# LMV324__20260912.net
KiCad netlist of a schematic drawn in Altium Designer
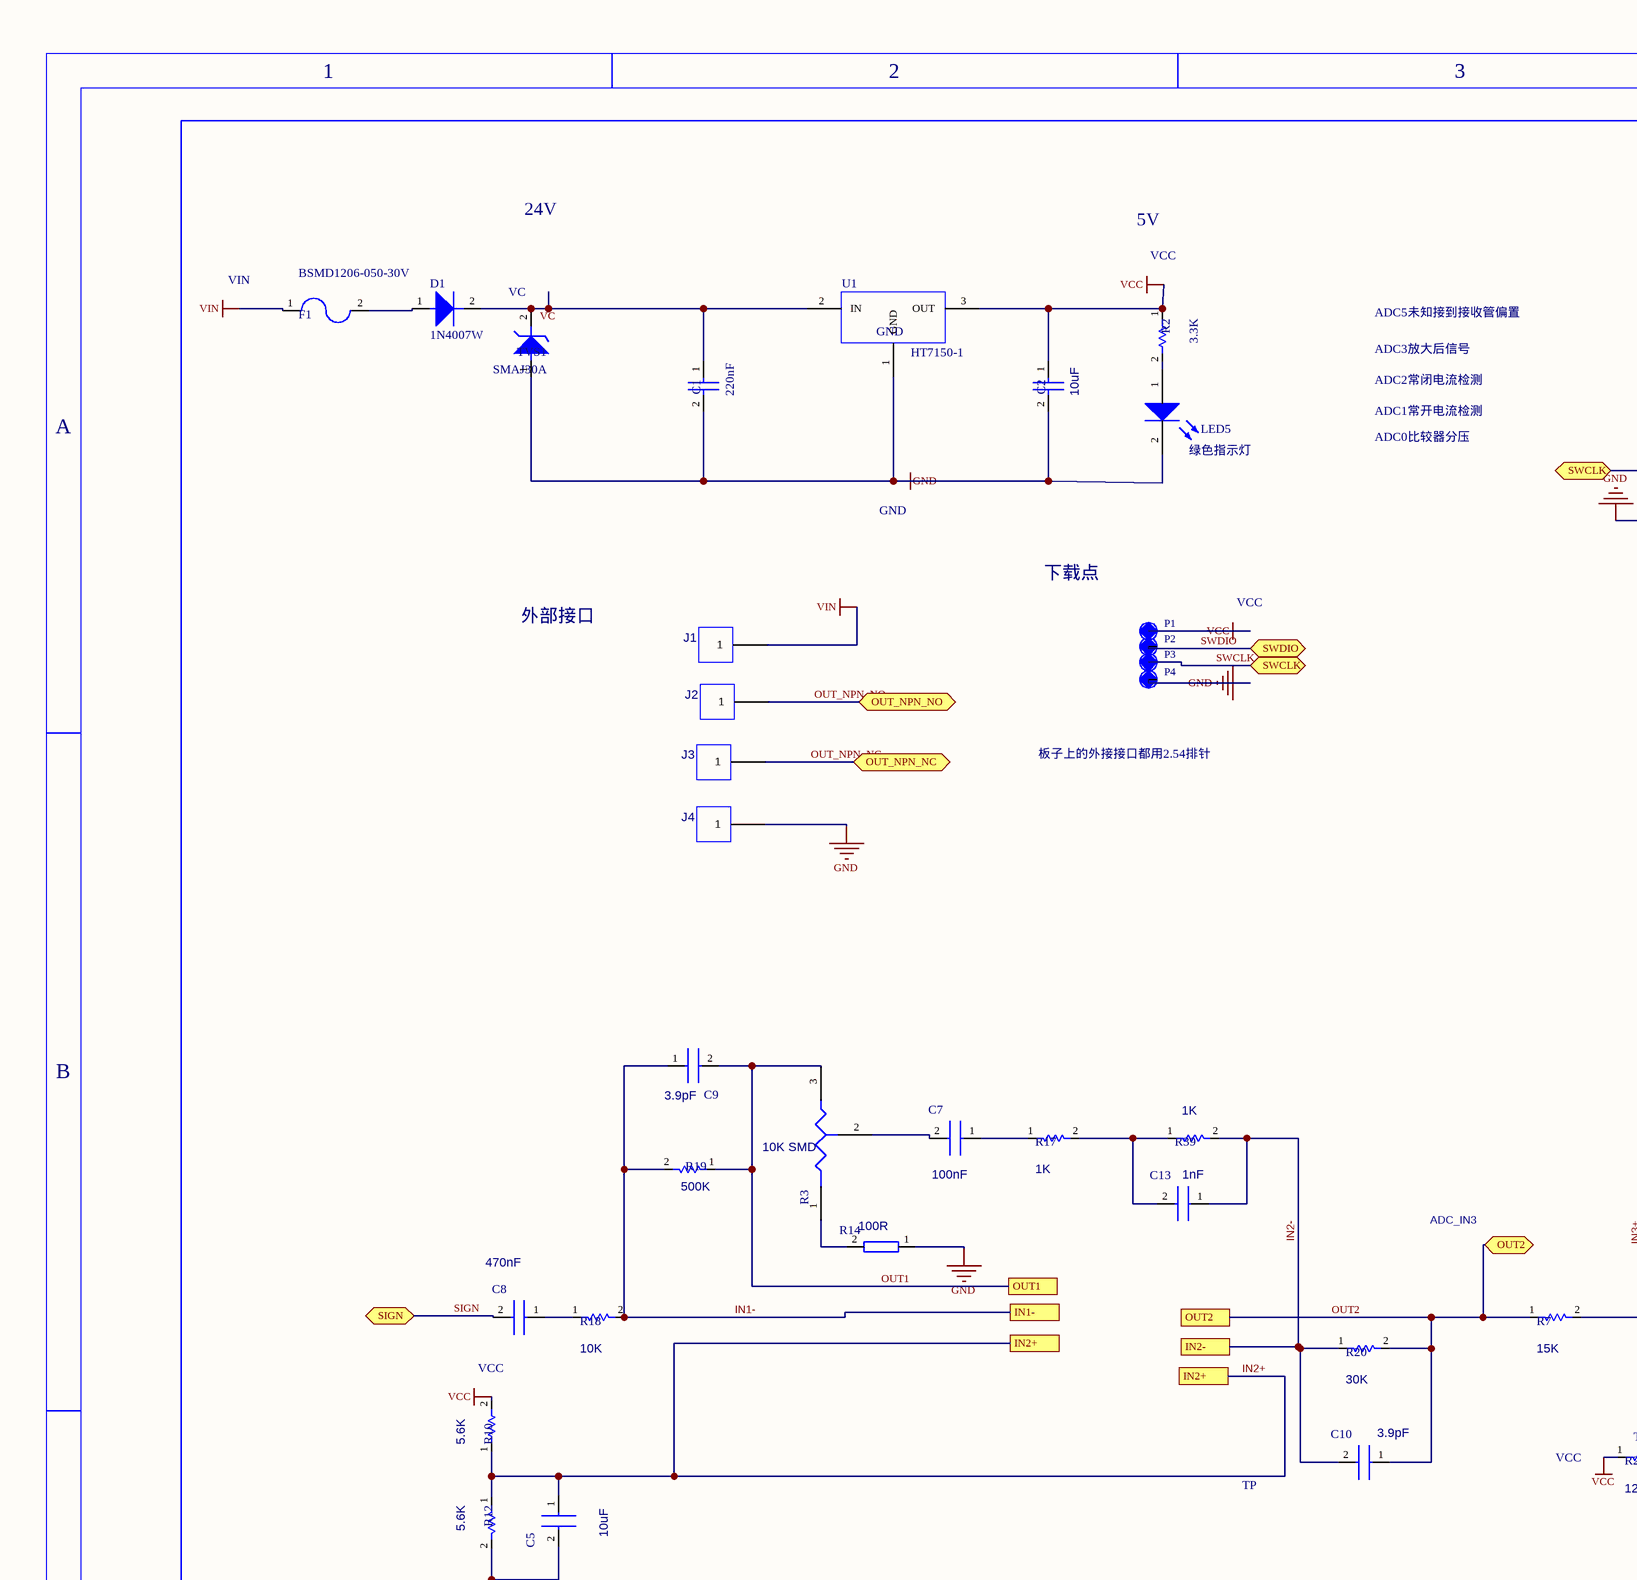
[diagram p0: LMV324对射发射板_20260912.SchDoc, top left]
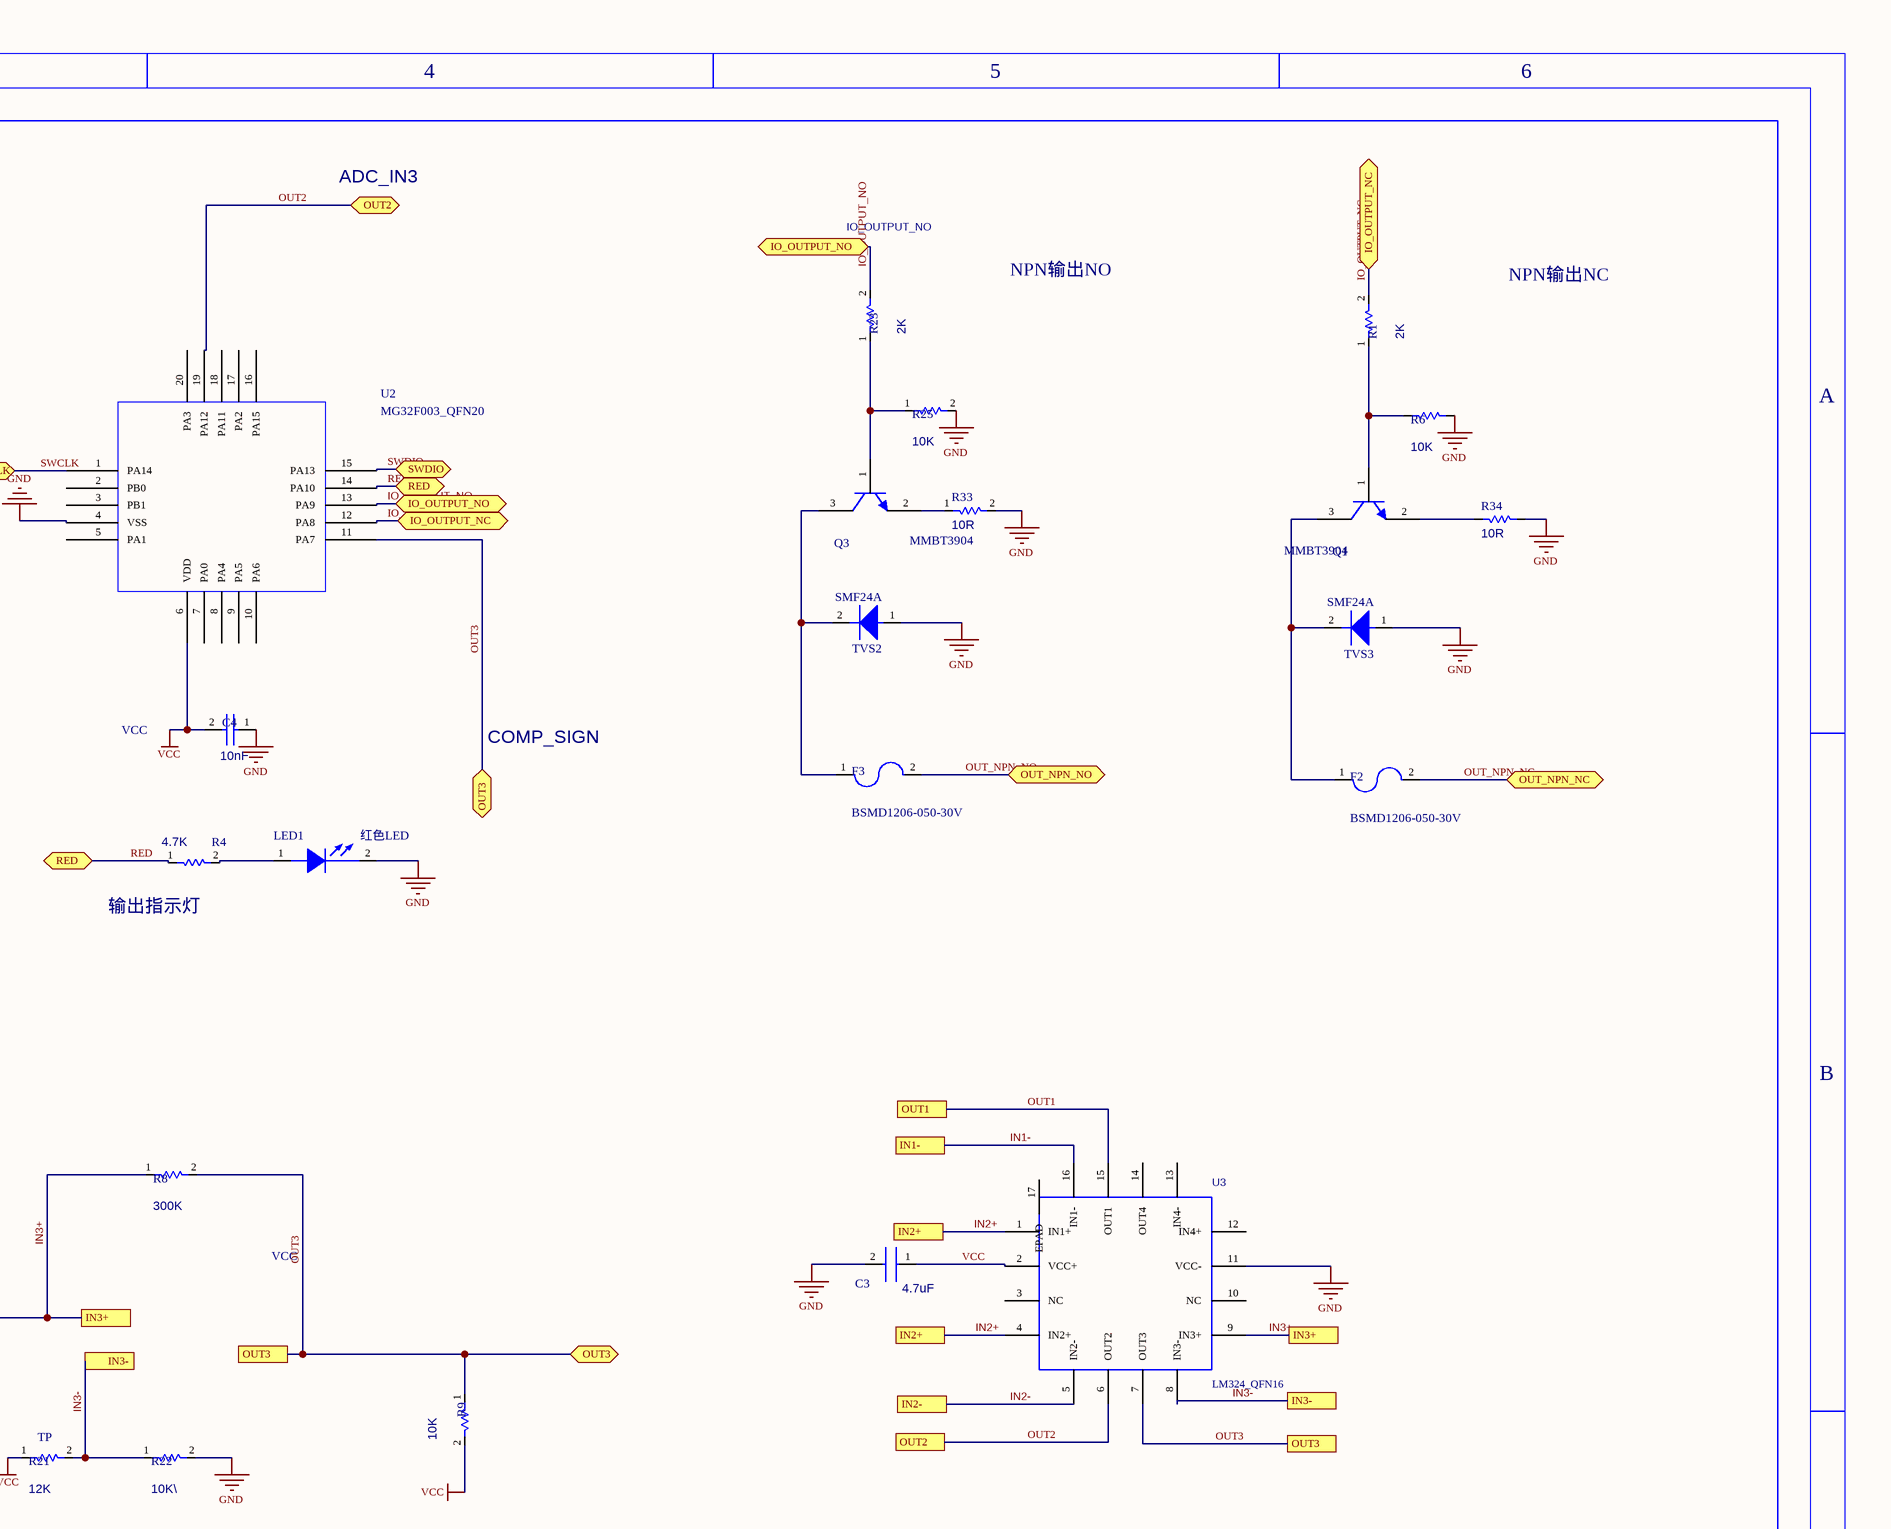
[diagram p1: LMV324对射发射板_20260912.SchDoc, top right]
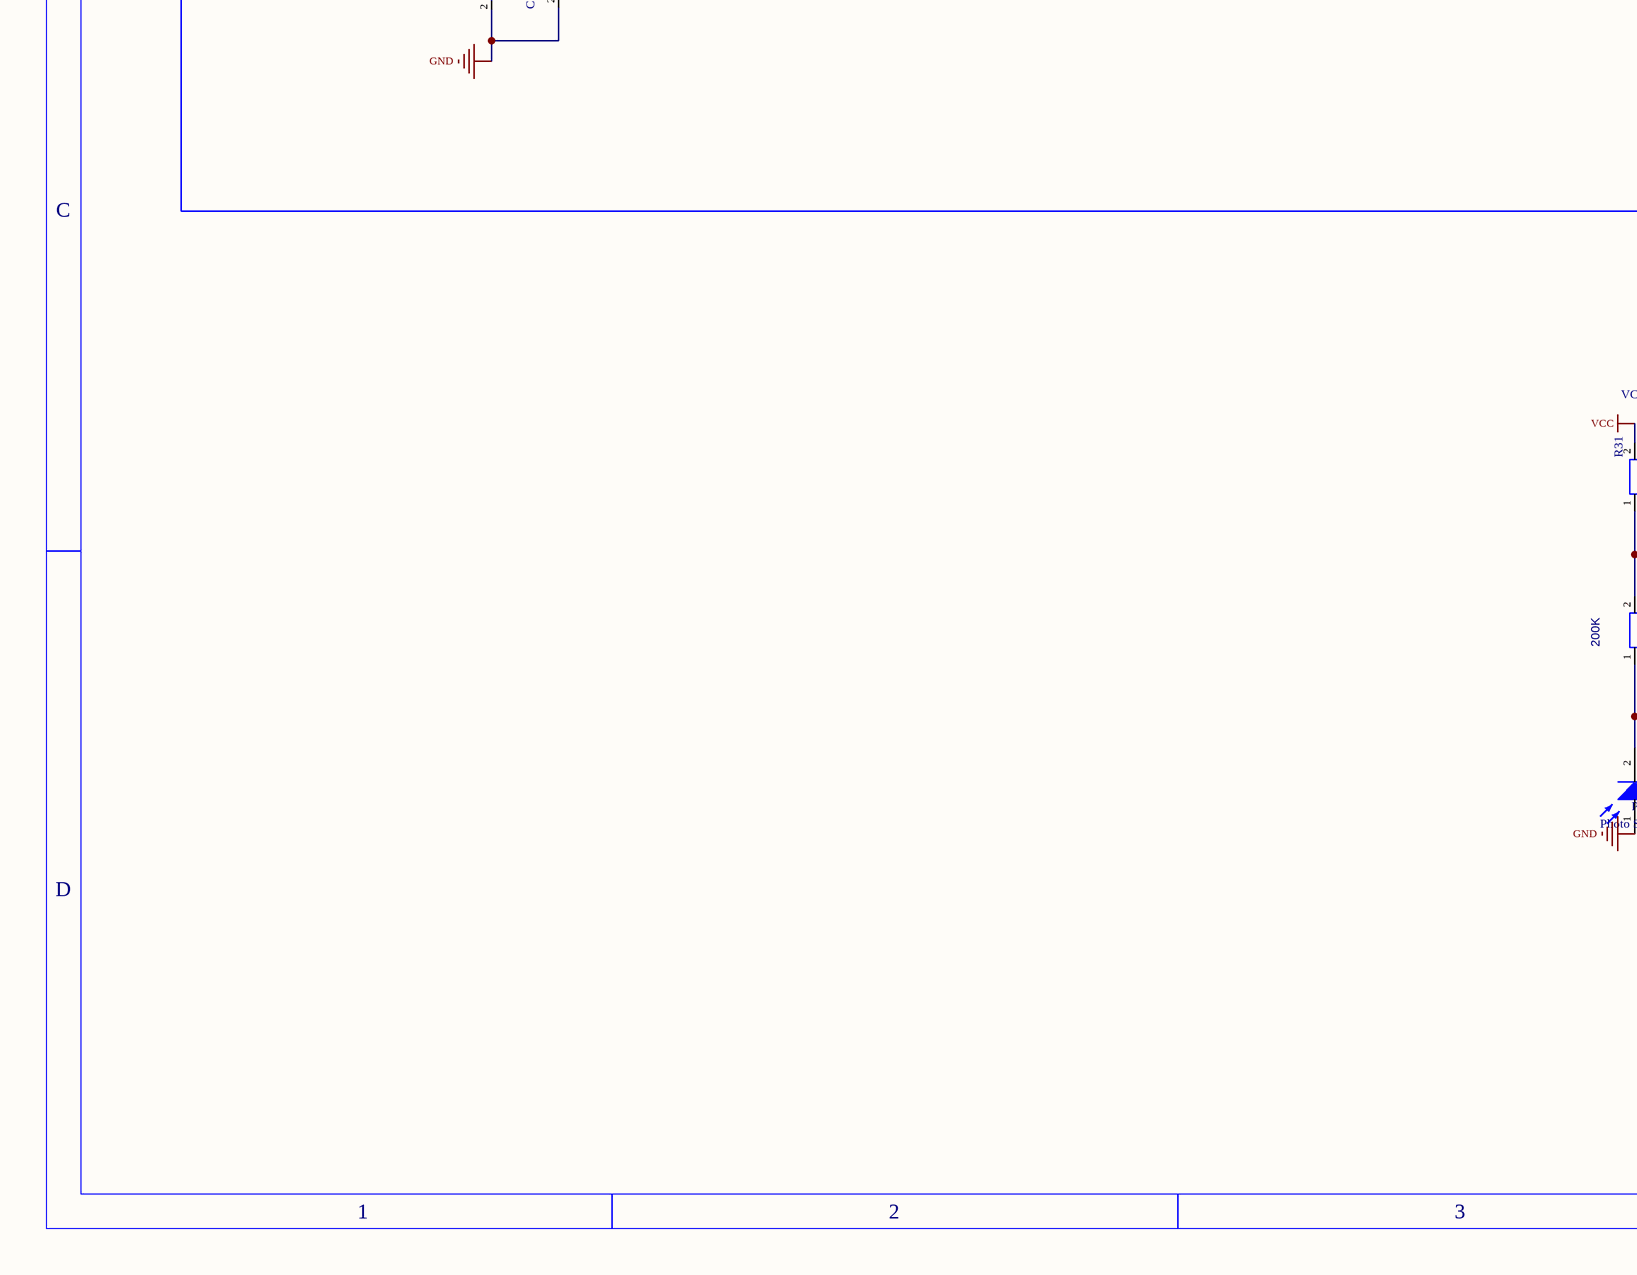
[diagram p2: LMV324对射发射板_20260912.SchDoc, bottom left]
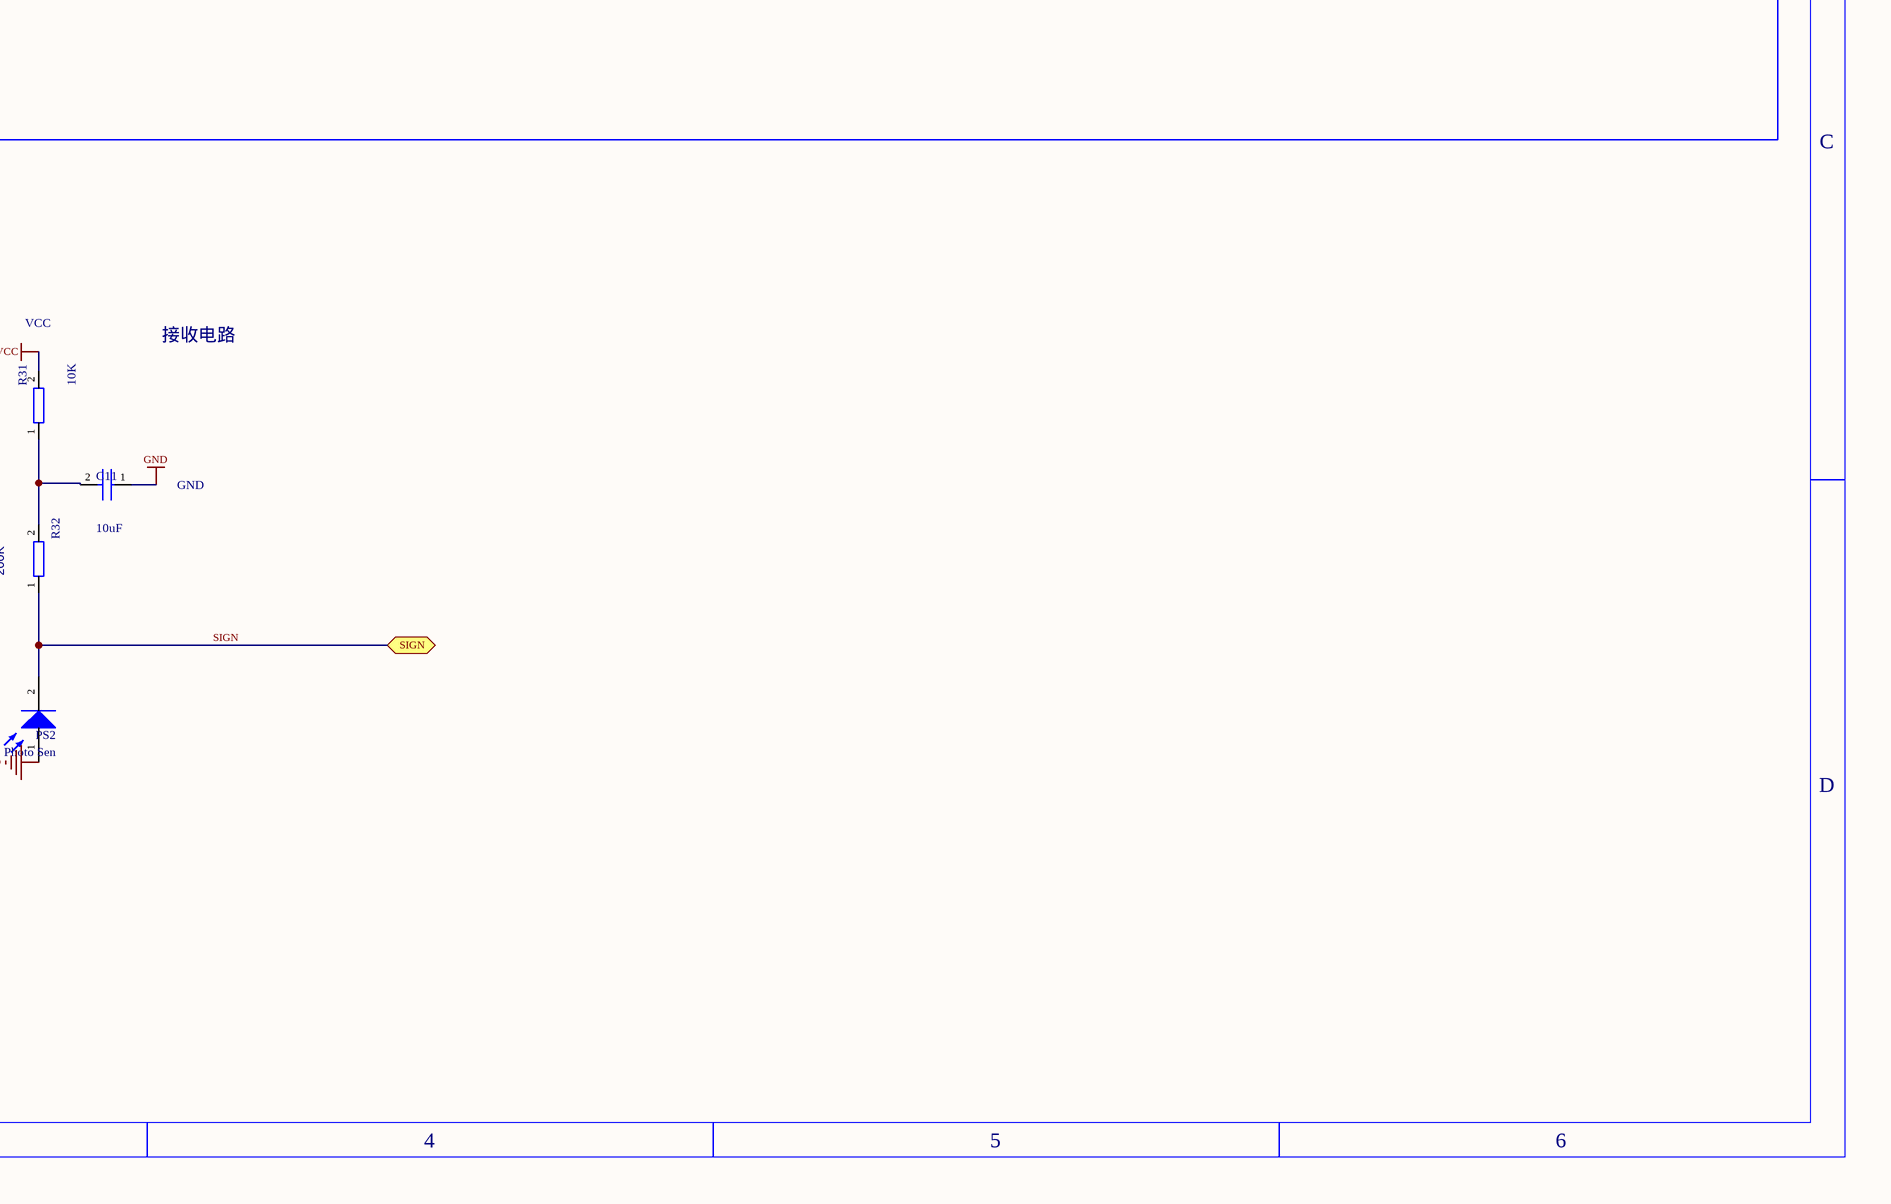
[diagram p3: LMV324对射发射板_20260912.SchDoc, bottom right]

(export (version "E")
  (design (tool "Eeschema 10.0.6"))
  (components
    (comp (ref "C1")
      (value "CAP")
      (footprint "C0603")
      (description "陶瓷电容")
      (libsource (lib "*") (part "CAP"))
    )
    (comp (ref "C2")
      (value "CAP")
      (footprint "C0603")
      (description "陶瓷电容")
      (libsource (lib "*") (part "CAP"))
    )
    (comp (ref "C3") (value "CAP_2") (footprint "C0603") (libsource (lib "*") (part "CAP_2")))
    (comp (ref "C4")
      (value "CAP")
      (footprint "C0603")
      (description "陶瓷电容")
      (libsource (lib "*") (part "CAP"))
    )
    (comp (ref "C5") (value "CAP_2") (footprint "C0603") (libsource (lib "*") (part "CAP_2")))
    (comp (ref "C7")
      (value "CAP0402")
      (footprint "0402C")
      (description "Capacitor")
      (libsource (lib "*") (part "CAP0402"))
    )
    (comp (ref "C8")
      (value "CAP0402")
      (footprint "0402C")
      (description "Capacitor")
      (libsource (lib "*") (part "CAP0402"))
    )
    (comp (ref "C9")
      (value "CAP0402")
      (footprint "0402C")
      (description "Capacitor")
      (libsource (lib "*") (part "CAP0402"))
    )
    (comp (ref "C10")
      (value "CAP0402")
      (footprint "0402C")
      (description "Capacitor")
      (libsource (lib "*") (part "CAP0402"))
    )
    (comp (ref "C11") (value "CAP_NP") (footprint "0603") (libsource (lib "*") (part "CAP_NP")))
    (comp (ref "C13")
      (value "CAP0402")
      (footprint "0402C")
      (description "Capacitor")
      (libsource (lib "*") (part "CAP0402"))
    )
    (comp (ref "D1")
      (value "DIODE")
      (footprint "WSOD-323")
      (description "Diode")
      (libsource (lib "*") (part "DIODE"))
    )
    (comp (ref "F1")
      (value "FUSE")
      (footprint "0603")
      (description "Fuse")
      (libsource (lib "") (part "FUSE_1"))
    )
    (comp (ref "F2")
      (value "FUSE")
      (footprint "0603")
      (description "Fuse")
      (libsource (lib "*") (part "FUSE"))
    )
    (comp (ref "F3")
      (value "FUSE")
      (footprint "0603")
      (description "Fuse")
      (libsource (lib "*") (part "FUSE"))
    )
    (comp (ref "J1")
      (value "FPAD_3C")
      (footprint "FPAD_3C")
      (description "Connector")
      (libsource (lib "*") (part "FPAD_3C"))
    )
    (comp (ref "J2")
      (value "FPAD_3C")
      (footprint "FPAD_3C")
      (description "Connector")
      (libsource (lib "*") (part "FPAD_3C"))
    )
    (comp (ref "J3")
      (value "FPAD_3C")
      (footprint "FPAD_3C")
      (description "Connector")
      (libsource (lib "*") (part "FPAD_3C"))
    )
    (comp (ref "J4")
      (value "FPAD_3C")
      (footprint "FPAD_3C")
      (description "Connector")
      (libsource (lib "*") (part "FPAD_3C"))
    )
    (comp (ref "LED1") (value "LED") (footprint "LED0603") (libsource (lib "*") (part "LED")))
    (comp (ref "LED5")
      (value "LED2")
      (footprint "LED0603")
      (description "Typical RED, GREEN, YELLOW, AMBER GaAs LED")
      (fields (field (name "PUBLISHER") "Altium Limited"))
      (libsource (lib "*") (part "LED2"))
    )
    (comp (ref "P1")
      (value "TEST_POINTB+")
      (footprint "TEST-POINT_D1.0")
      (libsource (lib "*") (part "TEST_POINTB+"))
    )
    (comp (ref "P2")
      (value "TEST_POINTB+")
      (footprint "TEST-POINT_D1.0")
      (libsource (lib "*") (part "TEST_POINTB+"))
    )
    (comp (ref "P3")
      (value "TEST_POINTB+")
      (footprint "TEST-POINT_D1.0")
      (libsource (lib "*") (part "TEST_POINTB+"))
    )
    (comp (ref "P4")
      (value "TEST_POINTB+")
      (footprint "TEST-POINT_D1.0")
      (libsource (lib "*") (part "TEST_POINTB+"))
    )
    (comp (ref "PS2")
      (value "PHOTO_SEN")
      (footprint "RXLED_SMD")
      (description "Photosensitive Diode")
      (fields (field (name "PUBLISHER") "Altium Limited"))
      (libsource (lib "*") (part "PHOTO_SEN"))
    )
    (comp (ref "Q1")
      (value "NPN")
      (footprint "SOT23/2")
      (description "NPN Bipolar Transistor")
      (fields (field (name "PUBLISHER") "Altium Limited"))
      (libsource (lib "*") (part "NPN"))
    )
    (comp (ref "Q3")
      (value "NPNSOT23")
      (footprint "SOT23/2")
      (description "NPN Bipolar Transistor")
      (fields (field (name "PUBLISHER") "Altium Limited"))
      (libsource (lib "*") (part "NPNSOT23"))
    )
    (comp (ref "R1") (value "RAS0402") (footprint "R0402") (libsource (lib "*") (part "RAS0402")))
    (comp (ref "R2") (value "RAS0402") (footprint "R0402") (libsource (lib "*") (part "RAS0402")))
    (comp (ref "R3")
      (value "10K SMD")
      (footprint "SMD")
      (description "Tapped Resistor")
      (fields (field (name "Comment") "ADJ_SMD") (field (name "PUBLISHER") "Altium Limited"))
      (libsource (lib "*") (part "ADJ_SMD"))
    )
    (comp (ref "R4") (value "RAS") (footprint "0603") (libsource (lib "*") (part "RAS")))
    (comp (ref "R6") (value "RAS0402") (footprint "R0402") (libsource (lib "") (part "RAS0402_1")))
    (comp (ref "R7") (value "RAS0402") (footprint "R0402") (libsource (lib "*") (part "RAS0402")))
    (comp (ref "R8") (value "RAS0402") (footprint "R0402") (libsource (lib "*") (part "RAS0402")))
    (comp (ref "R9") (value "RAS0402") (footprint "R0402") (libsource (lib "*") (part "RAS0402")))
    (comp (ref "R10") (value "RAS0402") (footprint "R0402") (libsource (lib "*") (part "RAS0402")))
    (comp (ref "R12") (value "RAS0402") (footprint "R0402") (libsource (lib "*") (part "RAS0402")))
    (comp (ref "R14") (value "RES") (footprint "R0603") (libsource (lib "*") (part "RES")))
    (comp (ref "R17") (value "RAS0402") (footprint "R0402") (libsource (lib "*") (part "RAS0402")))
    (comp (ref "R18") (value "RAS0402") (footprint "R0402") (libsource (lib "*") (part "RAS0402")))
    (comp (ref "R19") (value "RAS0402") (footprint "R0402") (libsource (lib "*") (part "RAS0402")))
    (comp (ref "R20") (value "RAS0402") (footprint "R0402") (libsource (lib "*") (part "RAS0402")))
    (comp (ref "R21") (value "RAS0402") (footprint "R0402") (libsource (lib "*") (part "RAS0402")))
    (comp (ref "R22") (value "RAS0402") (footprint "R0402") (libsource (lib "*") (part "RAS0402")))
    (comp (ref "R23") (value "RAS0402") (footprint "R0402") (libsource (lib "*") (part "RAS0402")))
    (comp (ref "R25") (value "RAS0402") (footprint "R0402") (libsource (lib "*") (part "RAS0402")))
    (comp (ref "R31") (value "R0402") (footprint "RES0402") (libsource (lib "*") (part "R0402")))
    (comp (ref "R32") (value "R0402") (footprint "RES0402") (libsource (lib "*") (part "R0402")))
    (comp (ref "R33") (value "RAS") (footprint "0603") (libsource (lib "*") (part "RAS")))
    (comp (ref "R34") (value "RAS") (footprint "0603") (libsource (lib "") (part "RAS_1")))
    (comp (ref "R39") (value "RAS0402") (footprint "R0402") (libsource (lib "*") (part "RAS0402")))
    (comp (ref "TVS1")
      (value "DIODE_V")
      (footprint "SOD_523")
      (description "Varactor Diode")
      (libsource (lib "*") (part "DIODE_V"))
    )
    (comp (ref "TVS2")
      (value "SOD523")
      (footprint "SOD_523")
      (description "Diode")
      (fields (field (name "PUBLISHER") "Altium Limited"))
      (libsource (lib "*") (part "SOD523"))
    )
    (comp (ref "TVS3")
      (value "SOD523")
      (footprint "SOD_523")
      (description "Diode")
      (fields (field (name "PUBLISHER") "Altium Limited"))
      (libsource (lib "*") (part "SOD523"))
    )
    (comp (ref "U1")
      (value "HT7530-1")
      (footprint "SOT89")
      (description "3.0V 100mA Low Power,  Low Dropout Voltage (LDO) Regulator")
      (fields (field (name "PUBLISHER") "Altium Limited"))
      (libsource (lib "*") (part "HT7530-1"))
    )
    (comp (ref "U2")
      (value "MG32F003-QFN20")
      (footprint "MG32F003_QFN20")
      (description "QFN20主控芯片")
      (libsource (lib "*") (part "MG32F003-QFN20"))
    )
    (comp (ref "U3")
      (value "LM324_QFN16")
      (footprint "LM324_QFN16")
      (libsource (lib "*") (part "LM324_QFN16"))
    )
  )
  (nets
    (net (code "1") (name "/IN1-") (class "Default")
      (node (ref "C9") (pin "1") (pinfunction "1_1") (pintype "passive"))
      (node (ref "R18") (pin "2") (pinfunction "2_2") (pintype "passive"))
      (node (ref "R19") (pin "2") (pinfunction "2_2") (pintype "passive"))
      (node (ref "U3") (pin "16") (pinfunction "IN1-_16") (pintype "passive"))
    )
    (net (code "2") (name "/IN2+") (class "Default")
      (node (ref "C5") (pin "1") (pinfunction "1_1") (pintype "passive"))
      (node (ref "R10") (pin "1") (pinfunction "1_1") (pintype "passive"))
      (node (ref "R12") (pin "1") (pinfunction "1_1") (pintype "passive"))
      (node (ref "U3") (pin "1") (pinfunction "IN1+_1") (pintype "passive"))
      (node (ref "U3") (pin "4") (pinfunction "IN2+_4") (pintype "passive"))
    )
    (net (code "3") (name "/IN2-") (class "Default")
      (node (ref "C10") (pin "2") (pinfunction "2_2") (pintype "passive"))
      (node (ref "C13") (pin "1") (pinfunction "1_1") (pintype "passive"))
      (node (ref "R20") (pin "1") (pinfunction "1_1") (pintype "passive"))
      (node (ref "R39") (pin "2") (pinfunction "2_2") (pintype "passive"))
      (node (ref "U3") (pin "5") (pinfunction "IN2-_5") (pintype "passive"))
    )
    (net (code "4") (name "/IN3+") (class "Default")
      (node (ref "R7") (pin "2") (pinfunction "2_2") (pintype "passive"))
      (node (ref "R8") (pin "1") (pinfunction "1_1") (pintype "passive"))
      (node (ref "U3") (pin "9") (pinfunction "IN3+_9") (pintype "passive"))
    )
    (net (code "5") (name "/IN3-") (class "Default")
      (node (ref "R21") (pin "2") (pinfunction "2_2") (pintype "passive"))
      (node (ref "R22") (pin "1") (pinfunction "1_1") (pintype "passive"))
      (node (ref "U3") (pin "8") (pinfunction "IN3-_8") (pintype "passive"))
    )
    (net (code "6") (name "/IO_OUTPUT_NC") (class "Default")
      (node (ref "R1") (pin "2") (pinfunction "2_2") (pintype "passive"))
      (node (ref "U2") (pin "12") (pinfunction "PA8_12") (pintype "passive"))
    )
    (net (code "7") (name "/IO_OUTPUT_NO") (class "Default")
      (node (ref "R23") (pin "2") (pinfunction "2_2") (pintype "passive"))
      (node (ref "U2") (pin "13") (pinfunction "PA9_13") (pintype "passive"))
    )
    (net (code "8") (name "/OUT1") (class "Default")
      (node (ref "C9") (pin "2") (pinfunction "2_2") (pintype "passive"))
      (node (ref "R19") (pin "1") (pinfunction "1_1") (pintype "passive"))
      (node (ref "R3") (pin "3") (pinfunction "A_3") (pintype "passive"))
      (node (ref "U3") (pin "15") (pinfunction "OUT1_15") (pintype "passive"))
    )
    (net (code "9") (name "/OUT2") (class "Default")
      (node (ref "C10") (pin "1") (pinfunction "1_1") (pintype "passive"))
      (node (ref "R20") (pin "2") (pinfunction "2_2") (pintype "passive"))
      (node (ref "R7") (pin "1") (pinfunction "1_1") (pintype "passive"))
      (node (ref "U2") (pin "19") (pinfunction "PA12_19") (pintype "passive"))
      (node (ref "U3") (pin "6") (pinfunction "OUT2_6") (pintype "passive"))
    )
    (net (code "10") (name "/OUT3") (class "Default")
      (node (ref "R8") (pin "2") (pinfunction "2_2") (pintype "passive"))
      (node (ref "R9") (pin "1") (pinfunction "1_1") (pintype "passive"))
      (node (ref "U2") (pin "11") (pinfunction "PA7_11") (pintype "passive"))
      (node (ref "U3") (pin "7") (pinfunction "OUT3_7") (pintype "passive"))
    )
    (net (code "11") (name "/OUT_NPN_NC") (class "Default")
      (node (ref "F2") (pin "2") (pinfunction "2_2") (pintype "passive"))
      (node (ref "J3") (pin "1") (pinfunction "1_1") (pintype "passive"))
    )
    (net (code "12") (name "/OUT_NPN_NO") (class "Default")
      (node (ref "F3") (pin "2") (pinfunction "2_2") (pintype "passive"))
      (node (ref "J2") (pin "1") (pinfunction "1_1") (pintype "passive"))
    )
    (net (code "13") (name "/RED") (class "Default")
      (node (ref "R4") (pin "1") (pinfunction "1_1") (pintype "passive"))
      (node (ref "U2") (pin "14") (pinfunction "PA10_14") (pintype "passive"))
    )
    (net (code "14") (name "/SIGN") (class "Default")
      (node (ref "C8") (pin "2") (pinfunction "2_2") (pintype "passive"))
      (node (ref "PS2") (pin "2") (pinfunction "K_2") (pintype "passive"))
      (node (ref "R32") (pin "1") (pinfunction "1_1") (pintype "passive"))
    )
    (net (code "15") (name "/SWCLK") (class "Default")
      (node (ref "P3") (pin "1") (pinfunction "1_1") (pintype "passive"))
      (node (ref "U2") (pin "1") (pinfunction "PA14_1") (pintype "passive"))
    )
    (net (code "16") (name "/SWDIO") (class "Default")
      (node (ref "P2") (pin "1") (pinfunction "1_1") (pintype "passive"))
      (node (ref "U2") (pin "15") (pinfunction "PA13_15") (pintype "passive"))
    )
    (net (code "17") (name "GND") (class "Default")
      (node (ref "C1") (pin "2") (pinfunction "2_2") (pintype "passive"))
      (node (ref "C11") (pin "1") (pinfunction "1_1") (pintype "passive"))
      (node (ref "C2") (pin "2") (pinfunction "2_2") (pintype "passive"))
      (node (ref "C3") (pin "2") (pinfunction "2_2") (pintype "passive"))
      (node (ref "C4") (pin "1") (pinfunction "1_1") (pintype "passive"))
      (node (ref "C5") (pin "2") (pinfunction "2_2") (pintype "passive"))
      (node (ref "J4") (pin "1") (pinfunction "1_1") (pintype "passive"))
      (node (ref "LED1") (pin "2") (pinfunction "CATHODE_2") (pintype "passive"))
      (node (ref "LED5") (pin "2") (pinfunction "K_2") (pintype "passive"))
      (node (ref "P4") (pin "1") (pinfunction "1_1") (pintype "passive"))
      (node (ref "PS2") (pin "1") (pinfunction "A_1") (pintype "passive"))
      (node (ref "R12") (pin "2") (pinfunction "2_2") (pintype "passive"))
      (node (ref "R14") (pin "1") (pinfunction "1_1") (pintype "passive"))
      (node (ref "R22") (pin "2") (pinfunction "2_2") (pintype "passive"))
      (node (ref "R25") (pin "2") (pinfunction "2_2") (pintype "passive"))
      (node (ref "R33") (pin "2") (pinfunction "2_2") (pintype "passive"))
      (node (ref "R34") (pin "2") (pinfunction "2_2") (pintype "passive"))
      (node (ref "R6") (pin "2") (pinfunction "2_2") (pintype "passive"))
      (node (ref "TVS1") (pin "1") (pinfunction "1_1") (pintype "passive"))
      (node (ref "TVS2") (pin "1") (pinfunction "A_1") (pintype "passive"))
      (node (ref "TVS3") (pin "1") (pinfunction "A_1") (pintype "passive"))
      (node (ref "U1") (pin "1") (pinfunction "GND_1") (pintype "power_in"))
      (node (ref "U2") (pin "4") (pinfunction "VSS_4") (pintype "passive"))
      (node (ref "U3") (pin "11") (pinfunction "VCC-_11") (pintype "passive"))
    )
    (net (code "18") (name "Net-(C7-Pad1)") (class "Default")
      (node (ref "C7") (pin "1") (pinfunction "1_1") (pintype "passive"))
      (node (ref "R17") (pin "1") (pinfunction "1_1") (pintype "passive"))
    )
    (net (code "19") (name "Net-(C8-Pad1)") (class "Default")
      (node (ref "C8") (pin "1") (pinfunction "1_1") (pintype "passive"))
      (node (ref "R18") (pin "1") (pinfunction "1_1") (pintype "passive"))
    )
    (net (code "20") (name "Net-(C11-Pad2)") (class "Default")
      (node (ref "C11") (pin "2") (pinfunction "2_2") (pintype "passive"))
      (node (ref "R31") (pin "1") (pinfunction "1_1") (pintype "passive"))
      (node (ref "R32") (pin "2") (pinfunction "2_2") (pintype "passive"))
    )
    (net (code "21") (name "Net-(C13-Pad2)") (class "Default")
      (node (ref "C13") (pin "2") (pinfunction "2_2") (pintype "passive"))
      (node (ref "R17") (pin "2") (pinfunction "2_2") (pintype "passive"))
      (node (ref "R39") (pin "1") (pinfunction "1_1") (pintype "passive"))
    )
    (net (code "22") (name "Net-(D1-A)") (class "Default")
      (node (ref "D1") (pin "1") (pinfunction "A_1") (pintype "passive"))
      (node (ref "F1") (pin "2") (pinfunction "2_2") (pintype "passive"))
    )
    (net (code "23") (name "Net-(LED1-ANODE)") (class "Default")
      (node (ref "LED1") (pin "1") (pinfunction "ANODE_1") (pintype "passive"))
      (node (ref "R4") (pin "2") (pinfunction "2_2") (pintype "passive"))
    )
    (net (code "24") (name "Net-(LED5-A)") (class "Default")
      (node (ref "LED5") (pin "1") (pinfunction "A_1") (pintype "passive"))
      (node (ref "R2") (pin "2") (pinfunction "2_2") (pintype "passive"))
    )
    (net (code "25") (name "Net-(Q1-B)") (class "Default")
      (node (ref "Q1") (pin "1") (pinfunction "B_1") (pintype "passive"))
      (node (ref "R1") (pin "1") (pinfunction "1_1") (pintype "passive"))
      (node (ref "R6") (pin "1") (pinfunction "1_1") (pintype "passive"))
    )
    (net (code "26") (name "Net-(Q1-C)") (class "Default")
      (node (ref "F2") (pin "1") (pinfunction "1_1") (pintype "passive"))
      (node (ref "Q1") (pin "3") (pinfunction "C_3") (pintype "passive"))
      (node (ref "TVS3") (pin "2") (pinfunction "K_2") (pintype "passive"))
    )
    (net (code "27") (name "Net-(Q1-E)") (class "Default")
      (node (ref "Q1") (pin "2") (pinfunction "E_2") (pintype "passive"))
      (node (ref "R34") (pin "1") (pinfunction "1_1") (pintype "passive"))
    )
    (net (code "28") (name "Net-(Q3-B)") (class "Default")
      (node (ref "Q3") (pin "1") (pinfunction "B_1") (pintype "passive"))
      (node (ref "R23") (pin "1") (pinfunction "1_1") (pintype "passive"))
      (node (ref "R25") (pin "1") (pinfunction "1_1") (pintype "passive"))
    )
    (net (code "29") (name "Net-(Q3-C)") (class "Default")
      (node (ref "F3") (pin "1") (pinfunction "1_1") (pintype "passive"))
      (node (ref "Q3") (pin "3") (pinfunction "C_3") (pintype "passive"))
      (node (ref "TVS2") (pin "2") (pinfunction "K_2") (pintype "passive"))
    )
    (net (code "30") (name "Net-(Q3-E)") (class "Default")
      (node (ref "Q3") (pin "2") (pinfunction "E_2") (pintype "passive"))
      (node (ref "R33") (pin "1") (pinfunction "1_1") (pintype "passive"))
    )
    (net (code "31") (name "Net-(R3-B)") (class "Default")
      (node (ref "R14") (pin "2") (pinfunction "2_2") (pintype "passive"))
      (node (ref "R3") (pin "1") (pinfunction "B_1") (pintype "passive"))
    )
    (net (code "32") (name "Net-(R3-TAP)") (class "Default")
      (node (ref "C7") (pin "2") (pinfunction "2_2") (pintype "passive"))
      (node (ref "R3") (pin "2") (pinfunction "TAP_2") (pintype "passive"))
    )
    (net (code "33") (name "VC") (class "Default")
      (node (ref "C1") (pin "1") (pinfunction "1_1") (pintype "passive"))
      (node (ref "D1") (pin "2") (pinfunction "K_2") (pintype "passive"))
      (node (ref "TVS1") (pin "2") (pinfunction "2_2") (pintype "passive"))
      (node (ref "U1") (pin "2") (pinfunction "IN_2") (pintype "power_in"))
    )
    (net (code "34") (name "VCC") (class "Default")
      (node (ref "C2") (pin "1") (pinfunction "1_1") (pintype "passive"))
      (node (ref "C3") (pin "1") (pinfunction "1_1") (pintype "passive"))
      (node (ref "C4") (pin "2") (pinfunction "2_2") (pintype "passive"))
      (node (ref "P1") (pin "1") (pinfunction "1_1") (pintype "passive"))
      (node (ref "R10") (pin "2") (pinfunction "2_2") (pintype "passive"))
      (node (ref "R2") (pin "1") (pinfunction "1_1") (pintype "passive"))
      (node (ref "R21") (pin "1") (pinfunction "1_1") (pintype "passive"))
      (node (ref "R31") (pin "2") (pinfunction "2_2") (pintype "passive"))
      (node (ref "R9") (pin "2") (pinfunction "2_2") (pintype "passive"))
      (node (ref "U1") (pin "3") (pinfunction "OUT_3") (pintype "power_in"))
      (node (ref "U2") (pin "6") (pinfunction "VDD_6") (pintype "passive"))
      (node (ref "U3") (pin "2") (pinfunction "VCC+_2") (pintype "passive"))
    )
    (net (code "35") (name "VIN") (class "Default")
      (node (ref "F1") (pin "1") (pinfunction "1_1") (pintype "passive"))
      (node (ref "J1") (pin "1") (pinfunction "1_1") (pintype "passive"))
    )
    (net (code "36") (name "unconnected-(U2-PA0-Pad7)") (class "Default")
      (node (ref "U2") (pin "7") (pinfunction "PA0_7") (pintype "passive"))
    )
    (net (code "37") (name "unconnected-(U2-PA1-Pad5)") (class "Default")
      (node (ref "U2") (pin "5") (pinfunction "PA1_5") (pintype "passive"))
    )
    (net (code "38") (name "unconnected-(U2-PA2-Pad17)") (class "Default")
      (node (ref "U2") (pin "17") (pinfunction "PA2_17") (pintype "passive"))
    )
    (net (code "39") (name "unconnected-(U2-PA3-Pad20)") (class "Default")
      (node (ref "U2") (pin "20") (pinfunction "PA3_20") (pintype "passive"))
    )
    (net (code "40") (name "unconnected-(U2-PA4-Pad8)") (class "Default")
      (node (ref "U2") (pin "8") (pinfunction "PA4_8") (pintype "passive"))
    )
    (net (code "41") (name "unconnected-(U2-PA5-Pad9)") (class "Default")
      (node (ref "U2") (pin "9") (pinfunction "PA5_9") (pintype "passive"))
    )
    (net (code "42") (name "unconnected-(U2-PA6-Pad10)") (class "Default")
      (node (ref "U2") (pin "10") (pinfunction "PA6_10") (pintype "passive"))
    )
    (net (code "43") (name "unconnected-(U2-PA11-Pad18)") (class "Default")
      (node (ref "U2") (pin "18") (pinfunction "PA11_18") (pintype "passive"))
    )
    (net (code "44") (name "unconnected-(U2-PA15-Pad16)") (class "Default")
      (node (ref "U2") (pin "16") (pinfunction "PA15_16") (pintype "passive"))
    )
    (net (code "45") (name "unconnected-(U2-PB0-Pad2)") (class "Default")
      (node (ref "U2") (pin "2") (pinfunction "PB0_2") (pintype "passive"))
    )
    (net (code "46") (name "unconnected-(U2-PB1-Pad3)") (class "Default")
      (node (ref "U2") (pin "3") (pinfunction "PB1_3") (pintype "passive"))
    )
    (net (code "47") (name "unconnected-(U3-EPAD-Pad17)") (class "Default")
      (node (ref "U3") (pin "17") (pinfunction "EPAD_17") (pintype "passive"))
    )
    (net (code "48") (name "unconnected-(U3-IN4+-Pad12)") (class "Default")
      (node (ref "U3") (pin "12") (pinfunction "IN4+_12") (pintype "passive"))
    )
    (net (code "49") (name "unconnected-(U3-IN4--Pad13)") (class "Default")
      (node (ref "U3") (pin "13") (pinfunction "IN4-_13") (pintype "passive"))
    )
    (net (code "50") (name "unconnected-(U3-NC-Pad3)") (class "Default")
      (node (ref "U3") (pin "3") (pinfunction "NC_3") (pintype "passive"))
    )
    (net (code "51") (name "unconnected-(U3-NC-Pad10)") (class "Default")
      (node (ref "U3") (pin "10") (pinfunction "NC_10") (pintype "passive"))
    )
    (net (code "52") (name "unconnected-(U3-OUT4-Pad14)") (class "Default")
      (node (ref "U3") (pin "14") (pinfunction "OUT4_14") (pintype "passive"))
    )
  )
)
